# Flipper_Zero_Dual_ESP32.net
KiCad netlist of a schematic drawn in EasyEDA
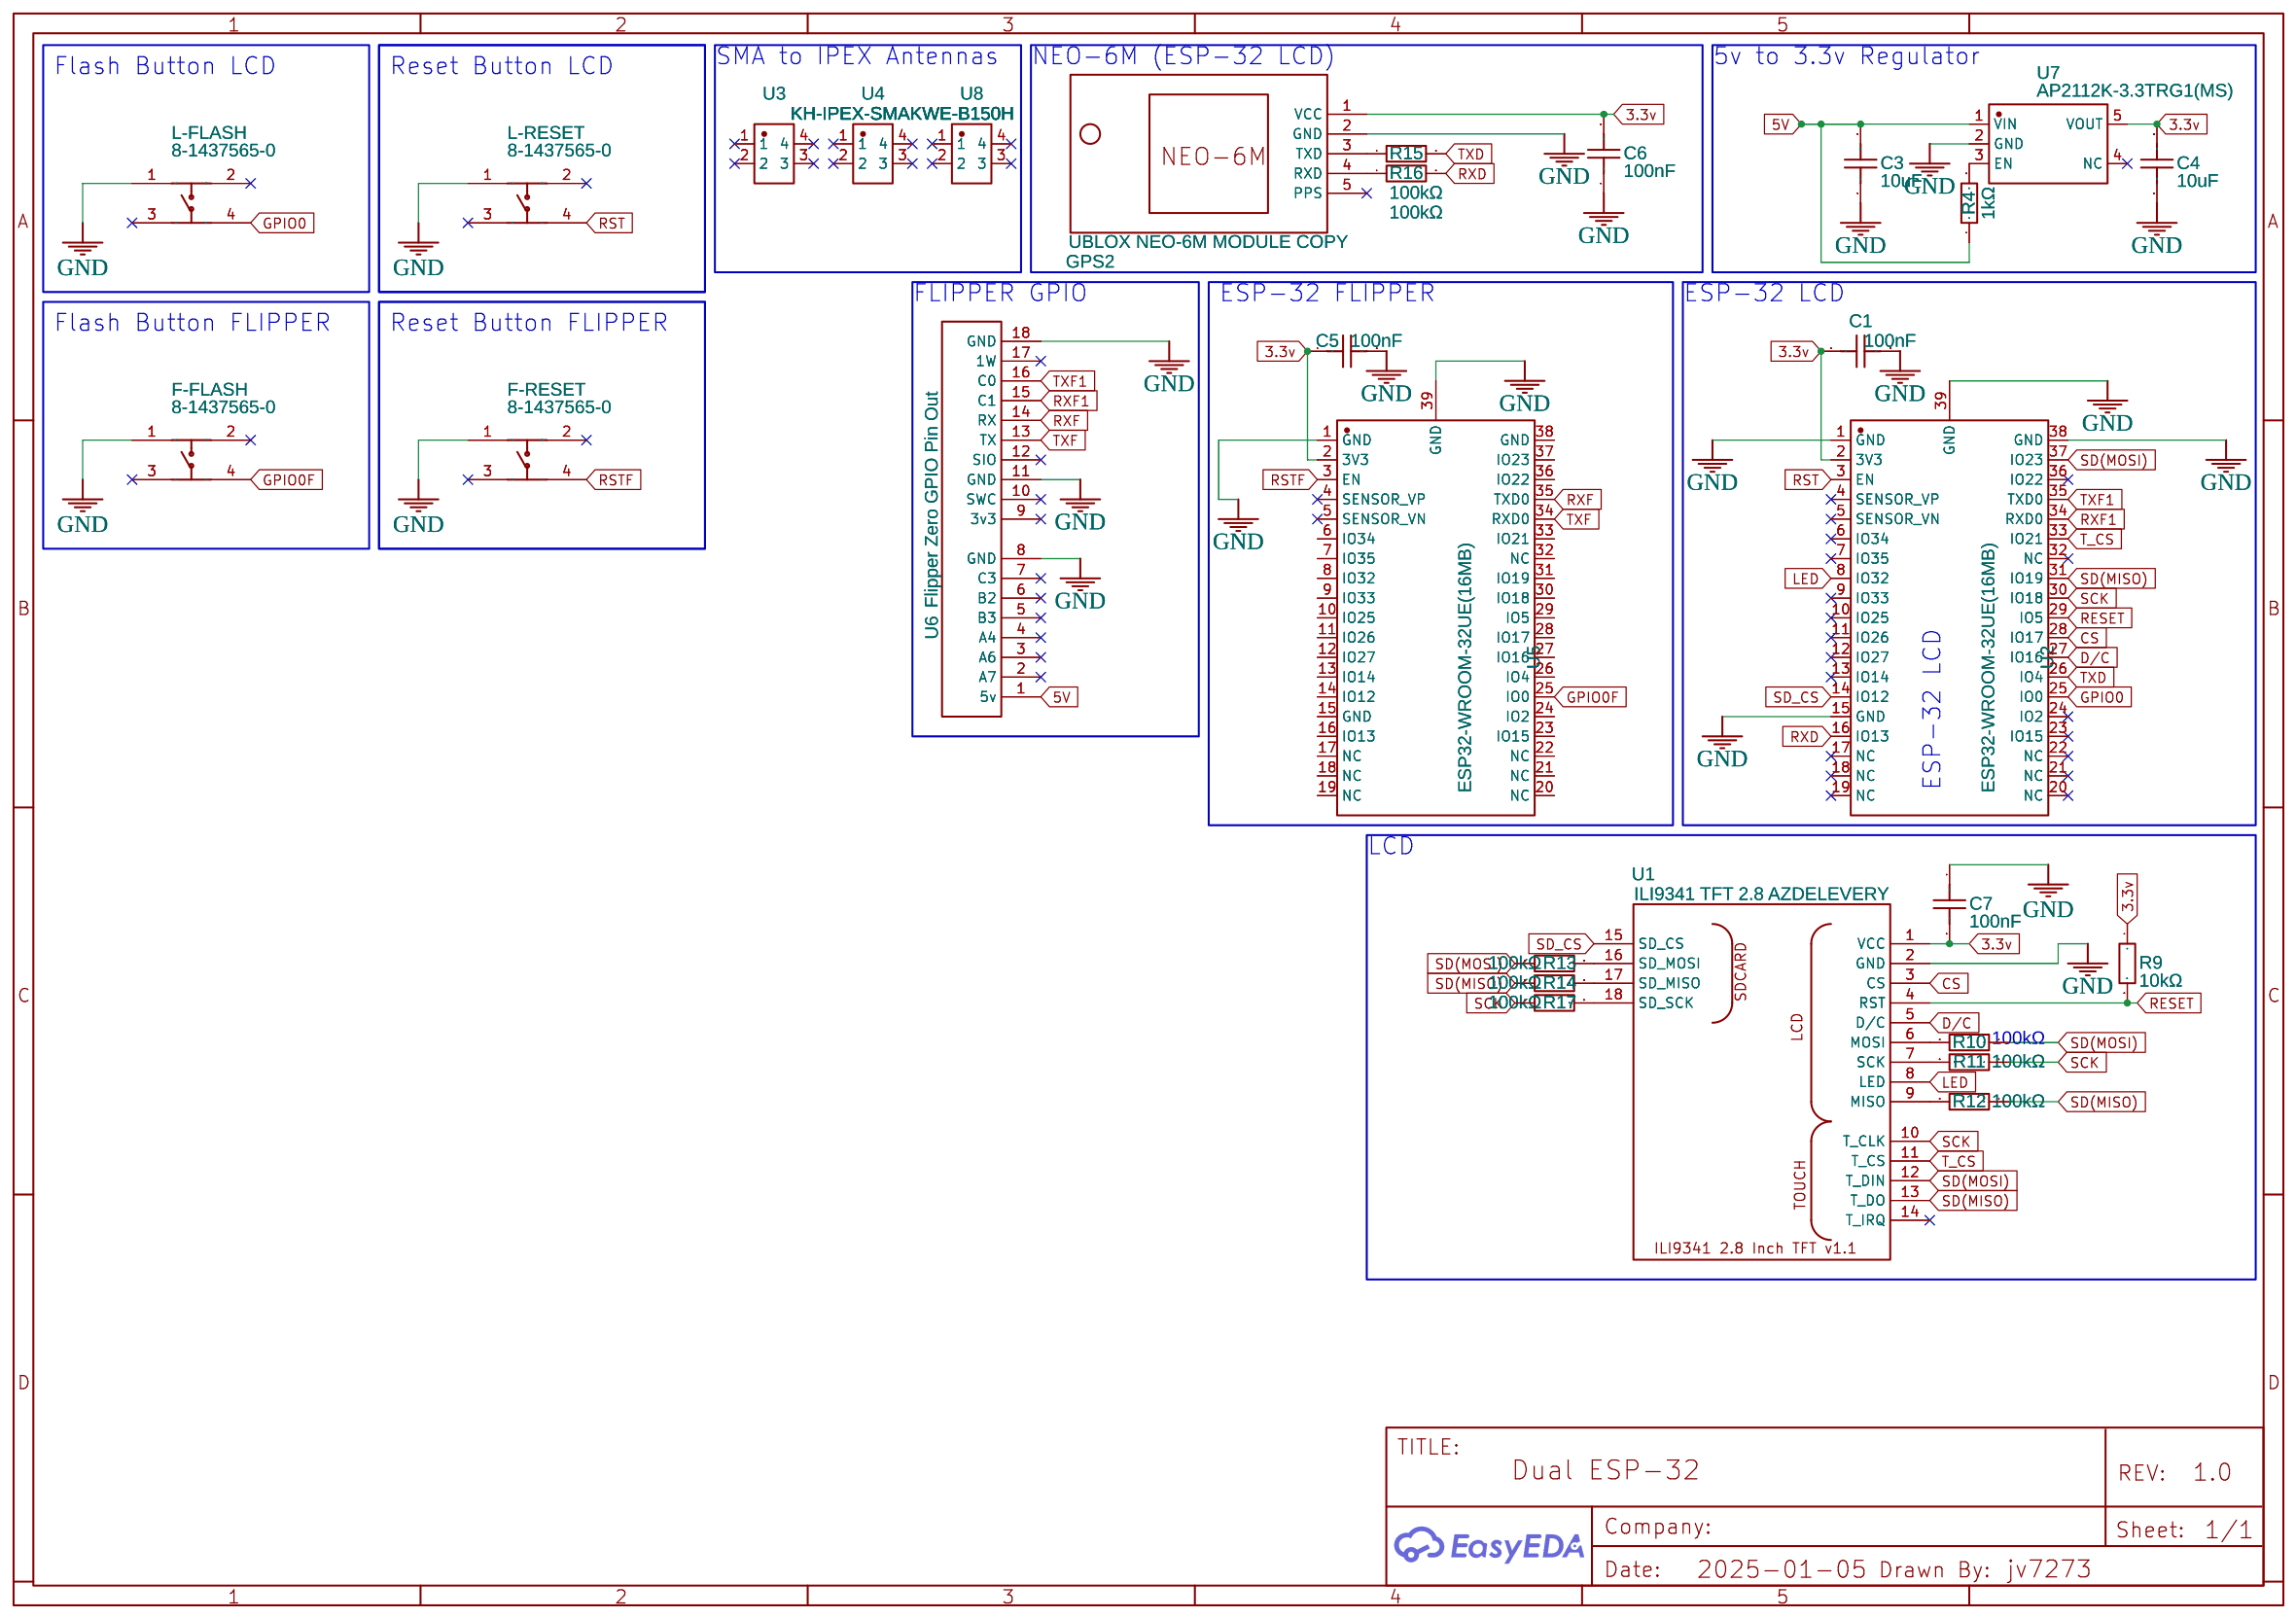
[diagram p0: schematic sheet]

(export (version "E")
  (design (tool "Eeschema 10.0.6"))
  (components
    (comp (ref "C1")
      (value "100nF")
      (fields
        (field (name "Manufacturer Part") "CL05B104KO5NNNC")
        (field (name "Manufacturer") "SAMSUNG(三星)")
      )
      (libsource (lib "") (part "CL05B104KO5NNNC"))
    )
    (comp (ref "C3")
      (value "10uF")
      (fields
        (field (name "Manufacturer Part") "CL10A106MQ8NNNC")
        (field (name "Manufacturer") "SAMSUNG(三星)")
      )
      (libsource (lib "") (part "CL10A106MQ8NNNC"))
    )
    (comp (ref "C4")
      (value "10uF")
      (fields
        (field (name "Manufacturer Part") "CL10A106MQ8NNNC")
        (field (name "Manufacturer") "SAMSUNG(三星)")
      )
      (libsource (lib "") (part "CL10A106MQ8NNNC"))
    )
    (comp (ref "C5")
      (value "100nF")
      (fields
        (field (name "Manufacturer Part") "CL05B104KO5NNNC")
        (field (name "Manufacturer") "SAMSUNG(三星)")
      )
      (libsource (lib "") (part "CL05B104KO5NNNC"))
    )
    (comp (ref "C6")
      (value "100nF")
      (fields
        (field (name "Manufacturer Part") "CL05B104KO5NNNC")
        (field (name "Manufacturer") "SAMSUNG(三星)")
      )
      (libsource (lib "") (part "CL05B104KO5NNNC_1"))
    )
    (comp (ref "C7")
      (value "100nF")
      (fields
        (field (name "Manufacturer Part") "CL05B104KO5NNNC")
        (field (name "Manufacturer") "SAMSUNG(三星)")
      )
      (libsource (lib "") (part "CL05B104KO5NNNC_2"))
    )
    (comp (ref "F-FLASH")
      (value "8-1437565-0")
      (fields (field (name "Manufacturer") "TE Connectivity(泰科电子)"))
      (libsource (lib "") (part "8-1437565-0_1"))
    )
    (comp (ref "F-RESET")
      (value "8-1437565-0")
      (fields (field (name "Manufacturer") "TE Connectivity(泰科电子)"))
      (libsource (lib "") (part "8-1437565-0"))
    )
    (comp (ref "GPS2")
      (value "UBLOX NEO-6M MODULE COPY")
      (libsource (lib "") (part "UBLOX NEO-6M MODULE COPY"))
    )
    (comp (ref "L-FLASH")
      (value "8-1437565-0")
      (fields (field (name "Manufacturer") "TE Connectivity(泰科电子)"))
      (libsource (lib "") (part "8-1437565-0_3"))
    )
    (comp (ref "L-RESET")
      (value "8-1437565-0")
      (fields (field (name "Manufacturer") "TE Connectivity(泰科电子)"))
      (libsource (lib "") (part "8-1437565-0_2"))
    )
    (comp (ref "R4")
      (value "1kΩ")
      (fields
        (field (name "Manufacturer Part") "1206W4J0102T5E")
        (field (name "Manufacturer") "UNI-ROYAL(厚声)")
      )
      (libsource (lib "") (part "1206W4J0102T5E"))
    )
    (comp (ref "R9")
      (value "10kΩ")
      (fields
        (field (name "Manufacturer Part") "1206W4J0103T5E")
        (field (name "Manufacturer") "UNI-ROYAL(厚声)")
      )
      (libsource (lib "") (part "1206W4J0103T5E"))
    )
    (comp (ref "R10")
      (value "100kΩ")
      (fields (field (name "Manufacturer Part") "RC0603FR-07100KL") (field (name "Manufacturer") "YAGEO(国巨)"))
      (libsource (lib "") (part "RC0603FR-07100KL_1"))
    )
    (comp (ref "R11")
      (value "100kΩ")
      (fields (field (name "Manufacturer Part") "RC0603FR-07100KL") (field (name "Manufacturer") "YAGEO(国巨)"))
      (libsource (lib "") (part "RC0603FR-07100KL_1"))
    )
    (comp (ref "R12")
      (value "100kΩ")
      (fields (field (name "Manufacturer Part") "RC0603FR-07100KL") (field (name "Manufacturer") "YAGEO(国巨)"))
      (libsource (lib "") (part "RC0603FR-07100KL_1"))
    )
    (comp (ref "R13")
      (value "100kΩ")
      (fields (field (name "Manufacturer Part") "RC0603FR-07100KL") (field (name "Manufacturer") "YAGEO(国巨)"))
      (libsource (lib "") (part "RC0603FR-07100KL"))
    )
    (comp (ref "R14")
      (value "100kΩ")
      (fields (field (name "Manufacturer Part") "RC0603FR-07100KL") (field (name "Manufacturer") "YAGEO(国巨)"))
      (libsource (lib "") (part "RC0603FR-07100KL"))
    )
    (comp (ref "R15")
      (value "100kΩ")
      (fields (field (name "Manufacturer Part") "RC0603FR-07100KL") (field (name "Manufacturer") "YAGEO(国巨)"))
      (libsource (lib "") (part "RC0603FR-07100KL"))
    )
    (comp (ref "R16")
      (value "100kΩ")
      (fields (field (name "Manufacturer Part") "RC0603FR-07100KL") (field (name "Manufacturer") "YAGEO(国巨)"))
      (libsource (lib "") (part "RC0603FR-07100KL"))
    )
    (comp (ref "R17")
      (value "100kΩ")
      (fields (field (name "Manufacturer Part") "RC0603FR-07100KL") (field (name "Manufacturer") "YAGEO(国巨)"))
      (libsource (lib "") (part "RC0603FR-07100KL"))
    )
    (comp (ref "U1")
      (value "ILI9341 TFT 2.8 AZDELEVERY")
      (libsource (lib "") (part "ILI9341 TFT 2.8 AZDELEVERY"))
    )
    (comp (ref "U2")
      (value "ESP32-WROOM-32UE(16MB)")
      (fields
        (field (name "Manufacturer Part") "ESP32-WROOM-32UE-N16")
        (field (name "Manufacturer") "ESPRESSIF(乐鑫)")
      )
      (libsource (lib "") (part "ESP32-WROOM-32UE(16MB)"))
    )
    (comp (ref "U3")
      (value "KH-IPEX-SMAKWE-B150H")
      (fields (field (name "Manufacturer") "kinghelm(金航标)"))
      (libsource (lib "") (part "KH-IPEX-SMAKWE-B150H"))
    )
    (comp (ref "U4")
      (value "KH-IPEX-SMAKWE-B150H")
      (fields (field (name "Manufacturer") "kinghelm(金航标)"))
      (libsource (lib "") (part "KH-IPEX-SMAKWE-B150H"))
    )
    (comp (ref "U5")
      (value "ESP32-WROOM-32UE(16MB)")
      (fields
        (field (name "Manufacturer Part") "ESP32-WROOM-32UE-N16")
        (field (name "Manufacturer") "ESPRESSIF(乐鑫)")
      )
      (libsource (lib "") (part "ESP32-WROOM-32UE(16MB)"))
    )
    (comp (ref "U6") (value "Flipper Zero GPIO Pin Out") (libsource (lib "") (part "Flipper Zero")))
    (comp (ref "U7")
      (value "AP2112K-3.3TRG1(MS)")
      (fields (field (name "Manufacturer") "MSKSEMI(美森科)"))
      (libsource (lib "") (part "AP2112K-3.3TRG1(MS)"))
    )
    (comp (ref "U8")
      (value "KH-IPEX-SMAKWE-B150H")
      (fields (field (name "Manufacturer") "kinghelm(金航标)"))
      (libsource (lib "") (part "KH-IPEX-SMAKWE-B150H"))
    )
  )
  (nets
    (net (code "1") (name "3.3v") (class "Default")
      (node (ref "C1") (pin "1") (pinfunction "1_1") (pintype "unspecified"))
      (node (ref "C4") (pin "2") (pinfunction "2_2") (pintype "unspecified"))
      (node (ref "C5") (pin "1") (pinfunction "1_1") (pintype "unspecified"))
      (node (ref "C6") (pin "2") (pinfunction "2_2") (pintype "unspecified"))
      (node (ref "C7") (pin "2") (pinfunction "2_2") (pintype "unspecified"))
      (node (ref "GPS2") (pin "1") (pinfunction "VCC_1") (pintype "unspecified"))
      (node (ref "R9") (pin "1") (pinfunction "1_1") (pintype "input"))
      (node (ref "U1") (pin "1") (pinfunction "VCC_1") (pintype "unspecified"))
      (node (ref "U2") (pin "2") (pinfunction "3V3_2") (pintype "unspecified"))
      (node (ref "U5") (pin "2") (pinfunction "3V3_2") (pintype "unspecified"))
      (node (ref "U7") (pin "5") (pinfunction "VOUT_5") (pintype "unspecified"))
    )
    (net (code "2") (name "5V") (class "Default")
      (node (ref "C3") (pin "2") (pinfunction "2_2") (pintype "unspecified"))
      (node (ref "R4") (pin "1") (pinfunction "1_1") (pintype "input"))
      (node (ref "U6") (pin "1") (pinfunction "5v_1") (pintype "unspecified"))
      (node (ref "U7") (pin "1") (pinfunction "VIN_1") (pintype "unspecified"))
    )
    (net (code "3") (name "CS") (class "Default")
      (node (ref "U1") (pin "3") (pinfunction "CS_3") (pintype "unspecified"))
      (node (ref "U2") (pin "28") (pinfunction "IO17_28") (pintype "unspecified"))
    )
    (net (code "4") (name "D{slash}C") (class "Default")
      (node (ref "U1") (pin "5") (pinfunction "D/C_5") (pintype "unspecified"))
      (node (ref "U2") (pin "27") (pinfunction "IO16_27") (pintype "unspecified"))
    )
    (net (code "5") (name "GND") (class "Default")
      (node (ref "C1") (pin "2") (pinfunction "2_2") (pintype "unspecified"))
      (node (ref "C3") (pin "1") (pinfunction "1_1") (pintype "unspecified"))
      (node (ref "C4") (pin "1") (pinfunction "1_1") (pintype "unspecified"))
      (node (ref "C5") (pin "2") (pinfunction "2_2") (pintype "unspecified"))
      (node (ref "C6") (pin "1") (pinfunction "1_1") (pintype "unspecified"))
      (node (ref "C7") (pin "1") (pinfunction "1_1") (pintype "unspecified"))
      (node (ref "F-FLASH") (pin "1") (pinfunction "1_1") (pintype "unspecified"))
      (node (ref "F-RESET") (pin "1") (pinfunction "1_1") (pintype "unspecified"))
      (node (ref "GPS2") (pin "2") (pinfunction "GND_2") (pintype "unspecified"))
      (node (ref "L-FLASH") (pin "1") (pinfunction "1_1") (pintype "unspecified"))
      (node (ref "L-RESET") (pin "1") (pinfunction "1_1") (pintype "unspecified"))
      (node (ref "U1") (pin "2") (pinfunction "GND_2") (pintype "unspecified"))
      (node (ref "U2") (pin "1") (pinfunction "GND_1") (pintype "unspecified"))
      (node (ref "U2") (pin "15") (pinfunction "GND_15") (pintype "unspecified"))
      (node (ref "U2") (pin "38") (pinfunction "GND_38") (pintype "unspecified"))
      (node (ref "U2") (pin "39") (pinfunction "GND_39") (pintype "unspecified"))
      (node (ref "U5") (pin "1") (pinfunction "GND_1") (pintype "unspecified"))
      (node (ref "U5") (pin "39") (pinfunction "GND_39") (pintype "unspecified"))
      (node (ref "U6") (pin "11") (pinfunction "GND_11") (pintype "unspecified"))
      (node (ref "U6") (pin "18") (pinfunction "GND_18") (pintype "unspecified"))
      (node (ref "U6") (pin "8") (pinfunction "GND_8") (pintype "unspecified"))
      (node (ref "U7") (pin "2") (pinfunction "GND_2") (pintype "unspecified"))
    )
    (net (code "6") (name "GPIO0") (class "Default")
      (node (ref "L-FLASH") (pin "4") (pinfunction "4_4") (pintype "unspecified"))
      (node (ref "U2") (pin "25") (pinfunction "IO0_25") (pintype "unspecified"))
    )
    (net (code "7") (name "GPIO0F") (class "Default")
      (node (ref "F-FLASH") (pin "4") (pinfunction "4_4") (pintype "unspecified"))
      (node (ref "U5") (pin "25") (pinfunction "IO0_25") (pintype "unspecified"))
    )
    (net (code "8") (name "LED") (class "Default")
      (node (ref "U1") (pin "8") (pinfunction "LED_8") (pintype "unspecified"))
      (node (ref "U2") (pin "8") (pinfunction "IO32_8") (pintype "unspecified"))
    )
    (net (code "9") (name "Net-(GPS2-RXD)") (class "Default")
      (node (ref "GPS2") (pin "4") (pinfunction "RXD_4") (pintype "unspecified"))
      (node (ref "R16") (pin "1") (pinfunction "1_1") (pintype "unspecified"))
    )
    (net (code "10") (name "Net-(GPS2-TXD)") (class "Default")
      (node (ref "GPS2") (pin "3") (pinfunction "TXD_3") (pintype "unspecified"))
      (node (ref "R15") (pin "1") (pinfunction "1_1") (pintype "unspecified"))
    )
    (net (code "11") (name "Net-(U1-MISO)") (class "Default")
      (node (ref "R12") (pin "2") (pinfunction "2_2") (pintype "unspecified"))
      (node (ref "U1") (pin "9") (pinfunction "MISO_9") (pintype "unspecified"))
    )
    (net (code "12") (name "Net-(U1-MOSI)") (class "Default")
      (node (ref "R10") (pin "2") (pinfunction "2_2") (pintype "unspecified"))
      (node (ref "U1") (pin "6") (pinfunction "MOSI_6") (pintype "unspecified"))
    )
    (net (code "13") (name "Net-(U1-SCK)") (class "Default")
      (node (ref "R11") (pin "2") (pinfunction "2_2") (pintype "unspecified"))
      (node (ref "U1") (pin "7") (pinfunction "SCK_7") (pintype "unspecified"))
    )
    (net (code "14") (name "Net-(U1-SD_MISO)") (class "Default")
      (node (ref "R14") (pin "2") (pinfunction "2_2") (pintype "unspecified"))
      (node (ref "U1") (pin "17") (pinfunction "SD_MISO_17") (pintype "unspecified"))
    )
    (net (code "15") (name "Net-(U1-SD_MOSI)") (class "Default")
      (node (ref "R13") (pin "2") (pinfunction "2_2") (pintype "unspecified"))
      (node (ref "U1") (pin "16") (pinfunction "SD_MOSI_16") (pintype "unspecified"))
    )
    (net (code "16") (name "Net-(U1-SD_SCK)") (class "Default")
      (node (ref "R17") (pin "2") (pinfunction "2_2") (pintype "unspecified"))
      (node (ref "U1") (pin "18") (pinfunction "SD_SCK_18") (pintype "unspecified"))
    )
    (net (code "17") (name "Net-(U7-EN)") (class "Default")
      (node (ref "R4") (pin "2") (pinfunction "2_2") (pintype "input"))
      (node (ref "U7") (pin "3") (pinfunction "EN_3") (pintype "unspecified"))
    )
    (net (code "18") (name "RESET") (class "Default")
      (node (ref "R9") (pin "2") (pinfunction "2_2") (pintype "input"))
      (node (ref "U1") (pin "4") (pinfunction "RST_4") (pintype "unspecified"))
      (node (ref "U2") (pin "29") (pinfunction "IO5_29") (pintype "unspecified"))
    )
    (net (code "19") (name "RST") (class "Default")
      (node (ref "L-RESET") (pin "4") (pinfunction "4_4") (pintype "unspecified"))
      (node (ref "U2") (pin "3") (pinfunction "EN_3") (pintype "unspecified"))
    )
    (net (code "20") (name "RSTF") (class "Default")
      (node (ref "F-RESET") (pin "4") (pinfunction "4_4") (pintype "unspecified"))
      (node (ref "U5") (pin "3") (pinfunction "EN_3") (pintype "unspecified"))
    )
    (net (code "21") (name "RXD") (class "Default")
      (node (ref "R16") (pin "2") (pinfunction "2_2") (pintype "unspecified"))
      (node (ref "U2") (pin "16") (pinfunction "IO13_16") (pintype "unspecified"))
    )
    (net (code "22") (name "RXF") (class "Default")
      (node (ref "U5") (pin "35") (pinfunction "TXD0_35") (pintype "unspecified"))
      (node (ref "U6") (pin "14") (pinfunction "RX_14") (pintype "unspecified"))
    )
    (net (code "23") (name "RXF1") (class "Default")
      (node (ref "U2") (pin "34") (pinfunction "RXD0_34") (pintype "unspecified"))
      (node (ref "U6") (pin "15") (pinfunction "C1_15") (pintype "unspecified"))
    )
    (net (code "24") (name "SCK") (class "Default")
      (node (ref "R11") (pin "1") (pinfunction "1_1") (pintype "unspecified"))
      (node (ref "R17") (pin "1") (pinfunction "1_1") (pintype "unspecified"))
      (node (ref "U1") (pin "10") (pinfunction "T_CLK_10") (pintype "unspecified"))
      (node (ref "U2") (pin "30") (pinfunction "IO18_30") (pintype "unspecified"))
    )
    (net (code "25") (name "SD(MISO)") (class "Default")
      (node (ref "R12") (pin "1") (pinfunction "1_1") (pintype "unspecified"))
      (node (ref "R14") (pin "1") (pinfunction "1_1") (pintype "unspecified"))
      (node (ref "U1") (pin "13") (pinfunction "T_DO_13") (pintype "unspecified"))
      (node (ref "U2") (pin "31") (pinfunction "IO19_31") (pintype "unspecified"))
    )
    (net (code "26") (name "SD(MOSI)") (class "Default")
      (node (ref "R10") (pin "1") (pinfunction "1_1") (pintype "unspecified"))
      (node (ref "R13") (pin "1") (pinfunction "1_1") (pintype "unspecified"))
      (node (ref "U1") (pin "12") (pinfunction "T_DIN_12") (pintype "unspecified"))
      (node (ref "U2") (pin "37") (pinfunction "IO23_37") (pintype "unspecified"))
    )
    (net (code "27") (name "SD_CS") (class "Default")
      (node (ref "U1") (pin "15") (pinfunction "SD_CS_15") (pintype "unspecified"))
      (node (ref "U2") (pin "14") (pinfunction "IO12_14") (pintype "unspecified"))
    )
    (net (code "28") (name "TXD") (class "Default")
      (node (ref "R15") (pin "2") (pinfunction "2_2") (pintype "unspecified"))
      (node (ref "U2") (pin "26") (pinfunction "IO4_26") (pintype "unspecified"))
    )
    (net (code "29") (name "TXF") (class "Default")
      (node (ref "U5") (pin "34") (pinfunction "RXD0_34") (pintype "unspecified"))
      (node (ref "U6") (pin "13") (pinfunction "TX_13") (pintype "unspecified"))
    )
    (net (code "30") (name "TXF1") (class "Default")
      (node (ref "U2") (pin "35") (pinfunction "TXD0_35") (pintype "unspecified"))
      (node (ref "U6") (pin "16") (pinfunction "C0_16") (pintype "unspecified"))
    )
    (net (code "31") (name "T_CS") (class "Default")
      (node (ref "U1") (pin "11") (pinfunction "T_CS_11") (pintype "unspecified"))
      (node (ref "U2") (pin "33") (pinfunction "IO21_33") (pintype "unspecified"))
    )
    (net (code "32") (name "unconnected-(F-FLASH-Pad2)") (class "Default")
      (node (ref "F-FLASH") (pin "2") (pinfunction "2_2") (pintype "unspecified+no_connect"))
    )
    (net (code "33") (name "unconnected-(F-FLASH-Pad3)") (class "Default")
      (node (ref "F-FLASH") (pin "3") (pinfunction "3_3") (pintype "unspecified+no_connect"))
    )
    (net (code "34") (name "unconnected-(F-RESET-Pad2)") (class "Default")
      (node (ref "F-RESET") (pin "2") (pinfunction "2_2") (pintype "unspecified+no_connect"))
    )
    (net (code "35") (name "unconnected-(F-RESET-Pad3)") (class "Default")
      (node (ref "F-RESET") (pin "3") (pinfunction "3_3") (pintype "unspecified+no_connect"))
    )
    (net (code "36") (name "unconnected-(GPS2-PPS-Pad5)") (class "Default")
      (node (ref "GPS2") (pin "5") (pinfunction "PPS_5") (pintype "unspecified+no_connect"))
    )
    (net (code "37") (name "unconnected-(L-FLASH-Pad2)") (class "Default")
      (node (ref "L-FLASH") (pin "2") (pinfunction "2_2") (pintype "unspecified+no_connect"))
    )
    (net (code "38") (name "unconnected-(L-FLASH-Pad3)") (class "Default")
      (node (ref "L-FLASH") (pin "3") (pinfunction "3_3") (pintype "unspecified+no_connect"))
    )
    (net (code "39") (name "unconnected-(L-RESET-Pad2)") (class "Default")
      (node (ref "L-RESET") (pin "2") (pinfunction "2_2") (pintype "unspecified+no_connect"))
    )
    (net (code "40") (name "unconnected-(L-RESET-Pad3)") (class "Default")
      (node (ref "L-RESET") (pin "3") (pinfunction "3_3") (pintype "unspecified+no_connect"))
    )
    (net (code "41") (name "unconnected-(U1-T_IRQ-Pad14)") (class "Default")
      (node (ref "U1") (pin "14") (pinfunction "T_IRQ_14") (pintype "unspecified+no_connect"))
    )
    (net (code "42") (name "unconnected-(U2-IO2-Pad24)") (class "Default")
      (node (ref "U2") (pin "24") (pinfunction "IO2_24") (pintype "unspecified+no_connect"))
    )
    (net (code "43") (name "unconnected-(U2-IO14-Pad13)") (class "Default")
      (node (ref "U2") (pin "13") (pinfunction "IO14_13") (pintype "unspecified+no_connect"))
    )
    (net (code "44") (name "unconnected-(U2-IO15-Pad23)") (class "Default")
      (node (ref "U2") (pin "23") (pinfunction "IO15_23") (pintype "unspecified+no_connect"))
    )
    (net (code "45") (name "unconnected-(U2-IO22-Pad36)") (class "Default")
      (node (ref "U2") (pin "36") (pinfunction "IO22_36") (pintype "unspecified+no_connect"))
    )
    (net (code "46") (name "unconnected-(U2-IO25-Pad10)") (class "Default")
      (node (ref "U2") (pin "10") (pinfunction "IO25_10") (pintype "unspecified+no_connect"))
    )
    (net (code "47") (name "unconnected-(U2-IO26-Pad11)") (class "Default")
      (node (ref "U2") (pin "11") (pinfunction "IO26_11") (pintype "unspecified+no_connect"))
    )
    (net (code "48") (name "unconnected-(U2-IO27-Pad12)") (class "Default")
      (node (ref "U2") (pin "12") (pinfunction "IO27_12") (pintype "unspecified+no_connect"))
    )
    (net (code "49") (name "unconnected-(U2-IO33-Pad9)") (class "Default")
      (node (ref "U2") (pin "9") (pinfunction "IO33_9") (pintype "unspecified+no_connect"))
    )
    (net (code "50") (name "unconnected-(U2-IO34-Pad6)") (class "Default")
      (node (ref "U2") (pin "6") (pinfunction "IO34_6") (pintype "unspecified+no_connect"))
    )
    (net (code "51") (name "unconnected-(U2-IO35-Pad7)") (class "Default")
      (node (ref "U2") (pin "7") (pinfunction "IO35_7") (pintype "unspecified+no_connect"))
    )
    (net (code "52") (name "unconnected-(U2-NC-Pad17)") (class "Default")
      (node (ref "U2") (pin "17") (pinfunction "NC_17") (pintype "unspecified+no_connect"))
    )
    (net (code "53") (name "unconnected-(U2-NC-Pad18)") (class "Default")
      (node (ref "U2") (pin "18") (pinfunction "NC_18") (pintype "unspecified+no_connect"))
    )
    (net (code "54") (name "unconnected-(U2-NC-Pad19)") (class "Default")
      (node (ref "U2") (pin "19") (pinfunction "NC_19") (pintype "unspecified+no_connect"))
    )
    (net (code "55") (name "unconnected-(U2-NC-Pad20)") (class "Default")
      (node (ref "U2") (pin "20") (pinfunction "NC_20") (pintype "unspecified+no_connect"))
    )
    (net (code "56") (name "unconnected-(U2-NC-Pad21)") (class "Default")
      (node (ref "U2") (pin "21") (pinfunction "NC_21") (pintype "unspecified+no_connect"))
    )
    (net (code "57") (name "unconnected-(U2-NC-Pad22)") (class "Default")
      (node (ref "U2") (pin "22") (pinfunction "NC_22") (pintype "unspecified+no_connect"))
    )
    (net (code "58") (name "unconnected-(U2-NC-Pad32)") (class "Default")
      (node (ref "U2") (pin "32") (pinfunction "NC_32") (pintype "unspecified+no_connect"))
    )
    (net (code "59") (name "unconnected-(U2-SENSOR_VN-Pad5)") (class "Default")
      (node (ref "U2") (pin "5") (pinfunction "SENSOR_VN_5") (pintype "unspecified+no_connect"))
    )
    (net (code "60") (name "unconnected-(U2-SENSOR_VP-Pad4)") (class "Default")
      (node (ref "U2") (pin "4") (pinfunction "SENSOR_VP_4") (pintype "unspecified+no_connect"))
    )
    (net (code "61") (name "unconnected-(U3-Pad1)") (class "Default")
      (node (ref "U3") (pin "1") (pinfunction "1_1") (pintype "unspecified+no_connect"))
    )
    (net (code "62") (name "unconnected-(U3-Pad2)") (class "Default")
      (node (ref "U3") (pin "2") (pinfunction "2_2") (pintype "unspecified+no_connect"))
    )
    (net (code "63") (name "unconnected-(U3-Pad3)") (class "Default")
      (node (ref "U3") (pin "3") (pinfunction "3_3") (pintype "unspecified+no_connect"))
    )
    (net (code "64") (name "unconnected-(U3-Pad4)") (class "Default")
      (node (ref "U3") (pin "4") (pinfunction "4_4") (pintype "unspecified+no_connect"))
    )
    (net (code "65") (name "unconnected-(U4-Pad1)") (class "Default")
      (node (ref "U4") (pin "1") (pinfunction "1_1") (pintype "unspecified+no_connect"))
    )
    (net (code "66") (name "unconnected-(U4-Pad2)") (class "Default")
      (node (ref "U4") (pin "2") (pinfunction "2_2") (pintype "unspecified+no_connect"))
    )
    (net (code "67") (name "unconnected-(U4-Pad3)") (class "Default")
      (node (ref "U4") (pin "3") (pinfunction "3_3") (pintype "unspecified+no_connect"))
    )
    (net (code "68") (name "unconnected-(U4-Pad4)") (class "Default")
      (node (ref "U4") (pin "4") (pinfunction "4_4") (pintype "unspecified+no_connect"))
    )
    (net (code "69") (name "unconnected-(U5-GND-Pad15)") (class "Default")
      (node (ref "U5") (pin "15") (pinfunction "GND_15") (pintype "unspecified"))
    )
    (net (code "70") (name "unconnected-(U5-GND-Pad38)") (class "Default")
      (node (ref "U5") (pin "38") (pinfunction "GND_38") (pintype "unspecified"))
    )
    (net (code "71") (name "unconnected-(U5-IO2-Pad24)") (class "Default")
      (node (ref "U5") (pin "24") (pinfunction "IO2_24") (pintype "unspecified"))
    )
    (net (code "72") (name "unconnected-(U5-IO4-Pad26)") (class "Default")
      (node (ref "U5") (pin "26") (pinfunction "IO4_26") (pintype "unspecified"))
    )
    (net (code "73") (name "unconnected-(U5-IO5-Pad29)") (class "Default")
      (node (ref "U5") (pin "29") (pinfunction "IO5_29") (pintype "unspecified"))
    )
    (net (code "74") (name "unconnected-(U5-IO12-Pad14)") (class "Default")
      (node (ref "U5") (pin "14") (pinfunction "IO12_14") (pintype "unspecified"))
    )
    (net (code "75") (name "unconnected-(U5-IO13-Pad16)") (class "Default")
      (node (ref "U5") (pin "16") (pinfunction "IO13_16") (pintype "unspecified"))
    )
    (net (code "76") (name "unconnected-(U5-IO14-Pad13)") (class "Default")
      (node (ref "U5") (pin "13") (pinfunction "IO14_13") (pintype "unspecified"))
    )
    (net (code "77") (name "unconnected-(U5-IO15-Pad23)") (class "Default")
      (node (ref "U5") (pin "23") (pinfunction "IO15_23") (pintype "unspecified"))
    )
    (net (code "78") (name "unconnected-(U5-IO16-Pad27)") (class "Default")
      (node (ref "U5") (pin "27") (pinfunction "IO16_27") (pintype "unspecified"))
    )
    (net (code "79") (name "unconnected-(U5-IO17-Pad28)") (class "Default")
      (node (ref "U5") (pin "28") (pinfunction "IO17_28") (pintype "unspecified"))
    )
    (net (code "80") (name "unconnected-(U5-IO18-Pad30)") (class "Default")
      (node (ref "U5") (pin "30") (pinfunction "IO18_30") (pintype "unspecified"))
    )
    (net (code "81") (name "unconnected-(U5-IO19-Pad31)") (class "Default")
      (node (ref "U5") (pin "31") (pinfunction "IO19_31") (pintype "unspecified"))
    )
    (net (code "82") (name "unconnected-(U5-IO21-Pad33)") (class "Default")
      (node (ref "U5") (pin "33") (pinfunction "IO21_33") (pintype "unspecified"))
    )
    (net (code "83") (name "unconnected-(U5-IO22-Pad36)") (class "Default")
      (node (ref "U5") (pin "36") (pinfunction "IO22_36") (pintype "unspecified"))
    )
    (net (code "84") (name "unconnected-(U5-IO23-Pad37)") (class "Default")
      (node (ref "U5") (pin "37") (pinfunction "IO23_37") (pintype "unspecified"))
    )
    (net (code "85") (name "unconnected-(U5-IO25-Pad10)") (class "Default")
      (node (ref "U5") (pin "10") (pinfunction "IO25_10") (pintype "unspecified"))
    )
    (net (code "86") (name "unconnected-(U5-IO26-Pad11)") (class "Default")
      (node (ref "U5") (pin "11") (pinfunction "IO26_11") (pintype "unspecified"))
    )
    (net (code "87") (name "unconnected-(U5-IO27-Pad12)") (class "Default")
      (node (ref "U5") (pin "12") (pinfunction "IO27_12") (pintype "unspecified"))
    )
    (net (code "88") (name "unconnected-(U5-IO32-Pad8)") (class "Default")
      (node (ref "U5") (pin "8") (pinfunction "IO32_8") (pintype "unspecified"))
    )
    (net (code "89") (name "unconnected-(U5-IO33-Pad9)") (class "Default")
      (node (ref "U5") (pin "9") (pinfunction "IO33_9") (pintype "unspecified"))
    )
    (net (code "90") (name "unconnected-(U5-IO34-Pad6)") (class "Default")
      (node (ref "U5") (pin "6") (pinfunction "IO34_6") (pintype "unspecified"))
    )
    (net (code "91") (name "unconnected-(U5-IO35-Pad7)") (class "Default")
      (node (ref "U5") (pin "7") (pinfunction "IO35_7") (pintype "unspecified"))
    )
    (net (code "92") (name "unconnected-(U5-NC-Pad17)") (class "Default")
      (node (ref "U5") (pin "17") (pinfunction "NC_17") (pintype "unspecified"))
    )
    (net (code "93") (name "unconnected-(U5-NC-Pad18)") (class "Default")
      (node (ref "U5") (pin "18") (pinfunction "NC_18") (pintype "unspecified"))
    )
    (net (code "94") (name "unconnected-(U5-NC-Pad19)") (class "Default")
      (node (ref "U5") (pin "19") (pinfunction "NC_19") (pintype "unspecified"))
    )
    (net (code "95") (name "unconnected-(U5-NC-Pad20)") (class "Default")
      (node (ref "U5") (pin "20") (pinfunction "NC_20") (pintype "unspecified"))
    )
    (net (code "96") (name "unconnected-(U5-NC-Pad21)") (class "Default")
      (node (ref "U5") (pin "21") (pinfunction "NC_21") (pintype "unspecified"))
    )
    (net (code "97") (name "unconnected-(U5-NC-Pad22)") (class "Default")
      (node (ref "U5") (pin "22") (pinfunction "NC_22") (pintype "unspecified"))
    )
    (net (code "98") (name "unconnected-(U5-NC-Pad32)") (class "Default")
      (node (ref "U5") (pin "32") (pinfunction "NC_32") (pintype "unspecified"))
    )
    (net (code "99") (name "unconnected-(U5-SENSOR_VN-Pad5)") (class "Default")
      (node (ref "U5") (pin "5") (pinfunction "SENSOR_VN_5") (pintype "unspecified+no_connect"))
    )
    (net (code "100") (name "unconnected-(U5-SENSOR_VP-Pad4)") (class "Default")
      (node (ref "U5") (pin "4") (pinfunction "SENSOR_VP_4") (pintype "unspecified+no_connect"))
    )
    (net (code "101") (name "unconnected-(U6-1W-Pad17)") (class "Default")
      (node (ref "U6") (pin "17") (pinfunction "1W_17") (pintype "unspecified+no_connect"))
    )
    (net (code "102") (name "unconnected-(U6-3v3-Pad9)") (class "Default")
      (node (ref "U6") (pin "9") (pinfunction "3v3_9") (pintype "unspecified+no_connect"))
    )
    (net (code "103") (name "unconnected-(U6-A4-Pad4)") (class "Default")
      (node (ref "U6") (pin "4") (pinfunction "A4_4") (pintype "unspecified+no_connect"))
    )
    (net (code "104") (name "unconnected-(U6-A6-Pad3)") (class "Default")
      (node (ref "U6") (pin "3") (pinfunction "A6_3") (pintype "unspecified+no_connect"))
    )
    (net (code "105") (name "unconnected-(U6-A7-Pad2)") (class "Default")
      (node (ref "U6") (pin "2") (pinfunction "A7_2") (pintype "unspecified+no_connect"))
    )
    (net (code "106") (name "unconnected-(U6-B2-Pad6)") (class "Default")
      (node (ref "U6") (pin "6") (pinfunction "B2_6") (pintype "unspecified+no_connect"))
    )
    (net (code "107") (name "unconnected-(U6-B3-Pad5)") (class "Default")
      (node (ref "U6") (pin "5") (pinfunction "B3_5") (pintype "unspecified+no_connect"))
    )
    (net (code "108") (name "unconnected-(U6-C3-Pad7)") (class "Default")
      (node (ref "U6") (pin "7") (pinfunction "C3_7") (pintype "unspecified+no_connect"))
    )
    (net (code "109") (name "unconnected-(U6-SIO-Pad12)") (class "Default")
      (node (ref "U6") (pin "12") (pinfunction "SIO_12") (pintype "unspecified+no_connect"))
    )
    (net (code "110") (name "unconnected-(U6-SWC-Pad10)") (class "Default")
      (node (ref "U6") (pin "10") (pinfunction "SWC_10") (pintype "unspecified+no_connect"))
    )
    (net (code "111") (name "unconnected-(U7-NC-Pad4)") (class "Default")
      (node (ref "U7") (pin "4") (pinfunction "NC_4") (pintype "unspecified+no_connect"))
    )
    (net (code "112") (name "unconnected-(U8-Pad1)") (class "Default")
      (node (ref "U8") (pin "1") (pinfunction "1_1") (pintype "unspecified+no_connect"))
    )
    (net (code "113") (name "unconnected-(U8-Pad2)") (class "Default")
      (node (ref "U8") (pin "2") (pinfunction "2_2") (pintype "unspecified+no_connect"))
    )
    (net (code "114") (name "unconnected-(U8-Pad3)") (class "Default")
      (node (ref "U8") (pin "3") (pinfunction "3_3") (pintype "unspecified+no_connect"))
    )
    (net (code "115") (name "unconnected-(U8-Pad4)") (class "Default")
      (node (ref "U8") (pin "4") (pinfunction "4_4") (pintype "unspecified+no_connect"))
    )
  )
)
